# MixerHF.net
KiCad netlist of a schematic drawn in Altium Designer
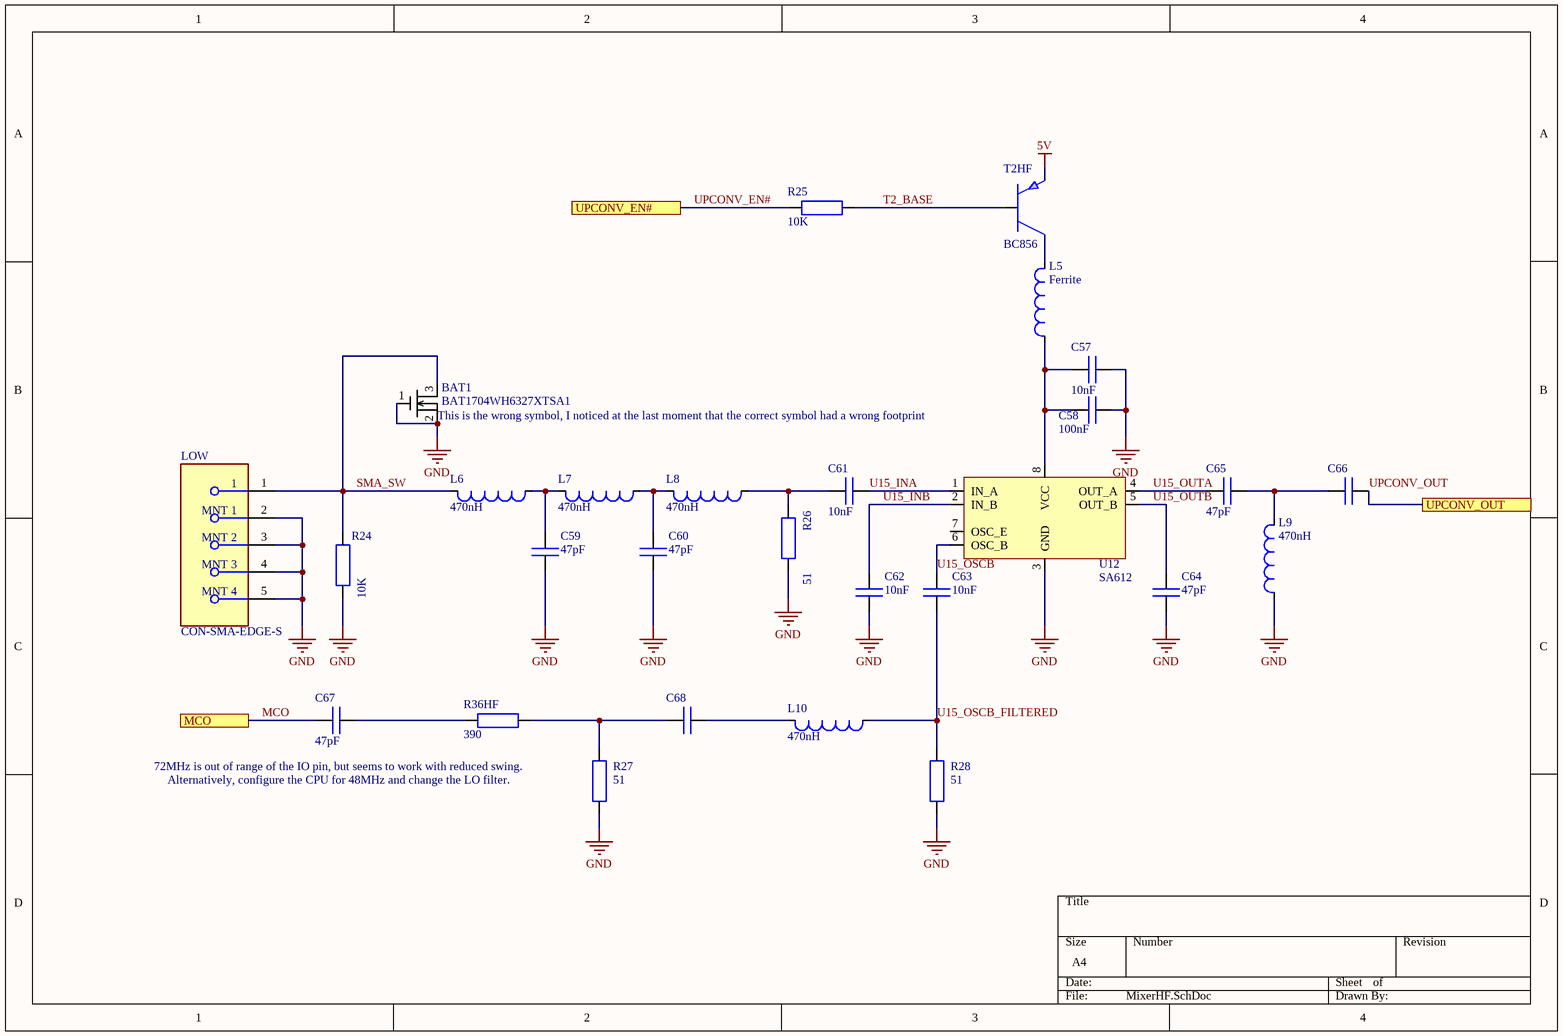
[diagram p0: MixerHF.SchDoc]

(export (version "E")
  (design (tool "Eeschema 10.0.6"))
  (components
    (comp (ref "BAT1")
      (value "BAT1704WH6327XTSA1")
      (footprint "SOT95P230X110-3N")
      (libsource (lib "library") (part "NX3008NBK"))
    )
    (comp (ref "C57")
      (value "10nF")
      (footprint "smd C0603_0.80")
      (description "smd capaciteit, verp.0603, 10nF")
      (fields (field (name "PART NUMBER") "CSMD603/10nF"))
      (libsource (lib "CDE_Library") (part "CSMD603/10nF"))
    )
    (comp (ref "C58")
      (value "100nF")
      (footprint "smd C0603_0.80")
      (description "smd capaciteit, verp.0603, 100nF")
      (fields (field (name "PART NUMBER") "CSMD603/100nF"))
      (libsource (lib "CDE_Library") (part "CSMD603/100nF"))
    )
    (comp (ref "C59")
      (value "47pF")
      (footprint "smd C0603_0.80")
      (description "smd capaciteit, verp.0603, 47pF")
      (fields (field (name "PART NUMBER") "CSMD603/47pF"))
      (libsource (lib "CDE_Library") (part "CSMD603/47pF"))
    )
    (comp (ref "C60")
      (value "47pF")
      (footprint "smd C0603_0.80")
      (description "smd capaciteit, verp.0603, 47pF")
      (fields (field (name "PART NUMBER") "CSMD603/47pF"))
      (libsource (lib "CDE_Library") (part "CSMD603/47pF"))
    )
    (comp (ref "C61")
      (value "10nF")
      (footprint "smd C0603_0.80")
      (description "smd capaciteit, verp.0603, 10nF")
      (fields (field (name "PART NUMBER") "CSMD603/10nF"))
      (libsource (lib "CDE_Library") (part "CSMD603/10nF"))
    )
    (comp (ref "C62")
      (value "10nF")
      (footprint "smd C0603_0.80")
      (description "smd capaciteit, verp.0603, 10nF")
      (fields (field (name "PART NUMBER") "CSMD603/10nF"))
      (libsource (lib "CDE_Library") (part "CSMD603/10nF"))
    )
    (comp (ref "C63")
      (value "10nF")
      (footprint "smd C0603_0.80")
      (description "smd capaciteit, verp.0603, 10nF")
      (fields (field (name "PART NUMBER") "CSMD603/10nF"))
      (libsource (lib "CDE_Library") (part "CSMD603/10nF"))
    )
    (comp (ref "C64")
      (value "47pF")
      (footprint "smd C0603_0.80")
      (description "smd capaciteit, verp.0603, 47pF")
      (fields (field (name "PART NUMBER") "CSMD603/47pF"))
      (libsource (lib "CDE_Library") (part "CSMD603/47pF"))
    )
    (comp (ref "C65")
      (value "47pF")
      (footprint "smd C0603_0.80")
      (description "smd capaciteit, verp.0603, 47pF")
      (fields (field (name "PART NUMBER") "CSMD603/47pF"))
      (libsource (lib "CDE_Library") (part "CSMD603/47pF"))
    )
    (comp (ref "C66")
      (value "~")
      (footprint "smd C0603_0.80")
      (description "smd capaciteit, verp.0603, 10pF")
      (fields (field (name "PART NUMBER") "CSMD603/10pF"))
      (libsource (lib "CDE_Library") (part "CSMD603/10pF"))
    )
    (comp (ref "C67")
      (value "47pF")
      (footprint "smd C0402")
      (description "smd capaciteit, verp.0402, 47pF")
      (fields (field (name "PART NUMBER") "CSMD402/47pF"))
      (libsource (lib "CDE_Library") (part "CSMD402/47pF"))
    )
    (comp (ref "C68")
      (value "~")
      (footprint "smd C0603_0.80")
      (description "smd capaciteit, verp.0603, 10pF")
      (fields (field (name "PART NUMBER") "CSMD603/10pF"))
      (libsource (lib "CDE_Library") (part "CSMD603/10pF"))
    )
    (comp (ref "L5")
      (value "Ferrite")
      (footprint "smd C0805")
      (description "Ferrite bead, 0805 package")
      (libsource (lib "CDE_Library") (part "Ferrite 0805"))
    )
    (comp (ref "L6")
      (value "470nH")
      (footprint "smd C0805")
      (description "smd spoel, verpakking 805, 470nH")
      (libsource (lib "CDE_Library") (part "SPL805/470nH"))
    )
    (comp (ref "L7")
      (value "470nH")
      (footprint "smd C0805")
      (description "smd spoel, verpakking 805, 470nH")
      (libsource (lib "CDE_Library") (part "SPL805/470nH"))
    )
    (comp (ref "L8")
      (value "470nH")
      (footprint "smd C0805")
      (description "smd spoel, verpakking 805, 470nH")
      (libsource (lib "CDE_Library") (part "SPL805/470nH"))
    )
    (comp (ref "L9")
      (value "470nH")
      (footprint "smd C0805")
      (description "smd spoel, verpakking 805, 470nH")
      (libsource (lib "CDE_Library") (part "SPL805/470nH"))
    )
    (comp (ref "L10")
      (value "470nH")
      (footprint "smd C0805")
      (description "smd spoel, verpakking 805, 470nH")
      (libsource (lib "CDE_Library") (part "SPL805/470nH"))
    )
    (comp (ref "LOW")
      (value "CON-SMA-EDGE-S")
      (footprint "FP-CON-SMA-EDGE-S-MFG")
      (description "CONN SMA JACK STR EDGE MNT")
      (fields
        (field (name "OCTOPART") "https://octopart.com/con-sma-edge-s-rf+solutions-70967450")
        (field (name "MANUFACTURER") "RF Solutions Ltd.")
      )
      (libsource (lib "Altium Content Vault") (part "a163d97a771fcdd2fd1f1a9264c171f"))
    )
    (comp (ref "R24")
      (value "10K")
      (footprint "smd C0603_0.45")
      (description "weerstand SMD603, 10K")
      (libsource (lib "CDE_Library") (part "10K/603"))
    )
    (comp (ref "R25")
      (value "10K")
      (footprint "smd C0603_0.45")
      (description "weerstand SMD603, 10K")
      (libsource (lib "CDE_Library") (part "10K/603"))
    )
    (comp (ref "R26")
      (value "51")
      (footprint "smd C0603_0.45")
      (description "weerstand SMD603, 51R")
      (libsource (lib "CDE_Library") (part "51R/603"))
    )
    (comp (ref "R27")
      (value "51")
      (footprint "smd C0603_0.45")
      (description "weerstand SMD603, 51R")
      (libsource (lib "CDE_Library") (part "51R/603"))
    )
    (comp (ref "R28")
      (value "51")
      (footprint "smd C0603_0.45")
      (description "weerstand SMD603, 51R")
      (libsource (lib "CDE_Library") (part "51R/603"))
    )
    (comp (ref "R36HF")
      (value "390")
      (footprint "smd C0603_0.45")
      (description "weerstand SMD603, 390R")
      (libsource (lib "CDE_Library") (part "390R/603"))
    )
    (comp (ref "T2HF")
      (value "BC856")
      (footprint "smd SOT-23")
      (description "PNP transistor, smd")
      (libsource (lib "CDE_Library") (part "BC856"))
    )
    (comp (ref "U12")
      (value "SA612")
      (footprint "SOIC127P600X175-8N")
      (libsource (lib "library") (part "SA612"))
    )
  )
  (nets
    (net (code "1") (name "/MCO") (class "Default") (node (ref "C67") (pin "2") (pintype "passive")))
    (net (code "2") (name "/SMA_SW") (class "Default")
      (node (ref "BAT1") (pin "3") (pinfunction "D_3") (pintype "passive"))
      (node (ref "L6") (pin "2") (pintype "passive"))
      (node (ref "LOW") (pin "1") (pinfunction "1_1") (pintype "passive"))
      (node (ref "R24") (pin "2") (pintype "passive"))
    )
    (net (code "3") (name "/T2_BASE") (class "Default")
      (node (ref "R25") (pin "2") (pintype "passive"))
      (node (ref "T2HF") (pin "1") (pintype "passive"))
    )
    (net (code "4") (name "/U15_INA") (class "Default")
      (node (ref "C61") (pin "1") (pintype "passive"))
      (node (ref "U12") (pin "1") (pinfunction "IN_A_1") (pintype "passive"))
    )
    (net (code "5") (name "/U15_INB") (class "Default")
      (node (ref "C62") (pin "1") (pintype "passive"))
      (node (ref "U12") (pin "2") (pinfunction "IN_B_2") (pintype "passive"))
    )
    (net (code "6") (name "/U15_OSCB") (class "Default")
      (node (ref "C63") (pin "1") (pintype "passive"))
      (node (ref "U12") (pin "6") (pinfunction "OSC_B_6") (pintype "passive"))
    )
    (net (code "7") (name "/U15_OSCB_FILTERED") (class "Default")
      (node (ref "C63") (pin "2") (pintype "passive"))
      (node (ref "L10") (pin "1") (pintype "passive"))
      (node (ref "R28") (pin "1") (pintype "passive"))
    )
    (net (code "8") (name "/U15_OUTA") (class "Default")
      (node (ref "C65") (pin "1") (pintype "passive"))
      (node (ref "U12") (pin "4") (pinfunction "OUT_A_4") (pintype "passive"))
    )
    (net (code "9") (name "/U15_OUTB") (class "Default")
      (node (ref "C64") (pin "2") (pintype "passive"))
      (node (ref "U12") (pin "5") (pinfunction "OUT_B_5") (pintype "passive"))
    )
    (net (code "10") (name "/UPCONV_EN#") (class "Default") (node (ref "R25") (pin "1") (pintype "passive")))
    (net (code "11") (name "/UPCONV_OUT") (class "Default") (node (ref "C66") (pin "2") (pintype "passive")))
    (net (code "12") (name "5V") (class "Default") (node (ref "T2HF") (pin "2") (pintype "passive")))
    (net (code "13") (name "GND") (class "Default")
      (node (ref "BAT1") (pin "1") (pinfunction "G_1") (pintype "passive"))
      (node (ref "BAT1") (pin "2") (pinfunction "S_2") (pintype "passive"))
      (node (ref "C57") (pin "1") (pintype "passive"))
      (node (ref "C58") (pin "1") (pintype "passive"))
      (node (ref "C59") (pin "1") (pintype "passive"))
      (node (ref "C60") (pin "1") (pintype "passive"))
      (node (ref "C62") (pin "2") (pintype "passive"))
      (node (ref "C64") (pin "1") (pintype "passive"))
      (node (ref "L9") (pin "1") (pintype "passive"))
      (node (ref "LOW") (pin "2") (pinfunction "MNT_1_2") (pintype "passive"))
      (node (ref "LOW") (pin "3") (pinfunction "MNT_2_3") (pintype "passive"))
      (node (ref "LOW") (pin "4") (pinfunction "MNT_3_4") (pintype "passive"))
      (node (ref "LOW") (pin "5") (pinfunction "MNT_4_5") (pintype "passive"))
      (node (ref "R24") (pin "1") (pintype "passive"))
      (node (ref "R26") (pin "1") (pintype "passive"))
      (node (ref "R27") (pin "2") (pintype "passive"))
      (node (ref "R28") (pin "2") (pintype "passive"))
      (node (ref "U12") (pin "3") (pinfunction "GND_3") (pintype "passive"))
    )
    (net (code "14") (name "Net-(C59-Pad2)") (class "Default")
      (node (ref "C59") (pin "2") (pintype "passive"))
      (node (ref "L6") (pin "1") (pintype "passive"))
      (node (ref "L7") (pin "2") (pintype "passive"))
    )
    (net (code "15") (name "Net-(C60-Pad2)") (class "Default")
      (node (ref "C60") (pin "2") (pintype "passive"))
      (node (ref "L7") (pin "1") (pintype "passive"))
      (node (ref "L8") (pin "2") (pintype "passive"))
    )
    (net (code "16") (name "Net-(C61-Pad2)") (class "Default")
      (node (ref "C61") (pin "2") (pintype "passive"))
      (node (ref "L8") (pin "1") (pintype "passive"))
      (node (ref "R26") (pin "2") (pintype "passive"))
    )
    (net (code "17") (name "Net-(C65-Pad2)") (class "Default")
      (node (ref "C65") (pin "2") (pintype "passive"))
      (node (ref "C66") (pin "1") (pintype "passive"))
      (node (ref "L9") (pin "2") (pintype "passive"))
    )
    (net (code "18") (name "Net-(C67-Pad1)") (class "Default")
      (node (ref "C67") (pin "1") (pintype "passive"))
      (node (ref "R36HF") (pin "2") (pintype "passive"))
    )
    (net (code "19") (name "Net-(C68-Pad1)") (class "Default")
      (node (ref "C68") (pin "1") (pintype "passive"))
      (node (ref "L10") (pin "2") (pintype "passive"))
    )
    (net (code "20") (name "Net-(C68-Pad2)") (class "Default")
      (node (ref "C68") (pin "2") (pintype "passive"))
      (node (ref "R27") (pin "1") (pintype "passive"))
      (node (ref "R36HF") (pin "1") (pintype "passive"))
    )
    (net (code "21") (name "Net-(L5-Pad2)") (class "Default")
      (node (ref "L5") (pin "2") (pintype "passive"))
      (node (ref "T2HF") (pin "3") (pintype "passive"))
    )
    (net (code "22") (name "Net-(U12-VCC)") (class "Default")
      (node (ref "C57") (pin "2") (pintype "passive"))
      (node (ref "C58") (pin "2") (pintype "passive"))
      (node (ref "L5") (pin "1") (pintype "passive"))
      (node (ref "U12") (pin "8") (pinfunction "VCC_8") (pintype "passive"))
    )
    (net (code "23") (name "unconnected-(U12-OSC_E-Pad7)") (class "Default")
      (node (ref "U12") (pin "7") (pinfunction "OSC_E_7") (pintype "passive"))
    )
  )
)
